# ethernet_ipphone_sch.net
KiCad netlist of a schematic drawn in Altium Designer
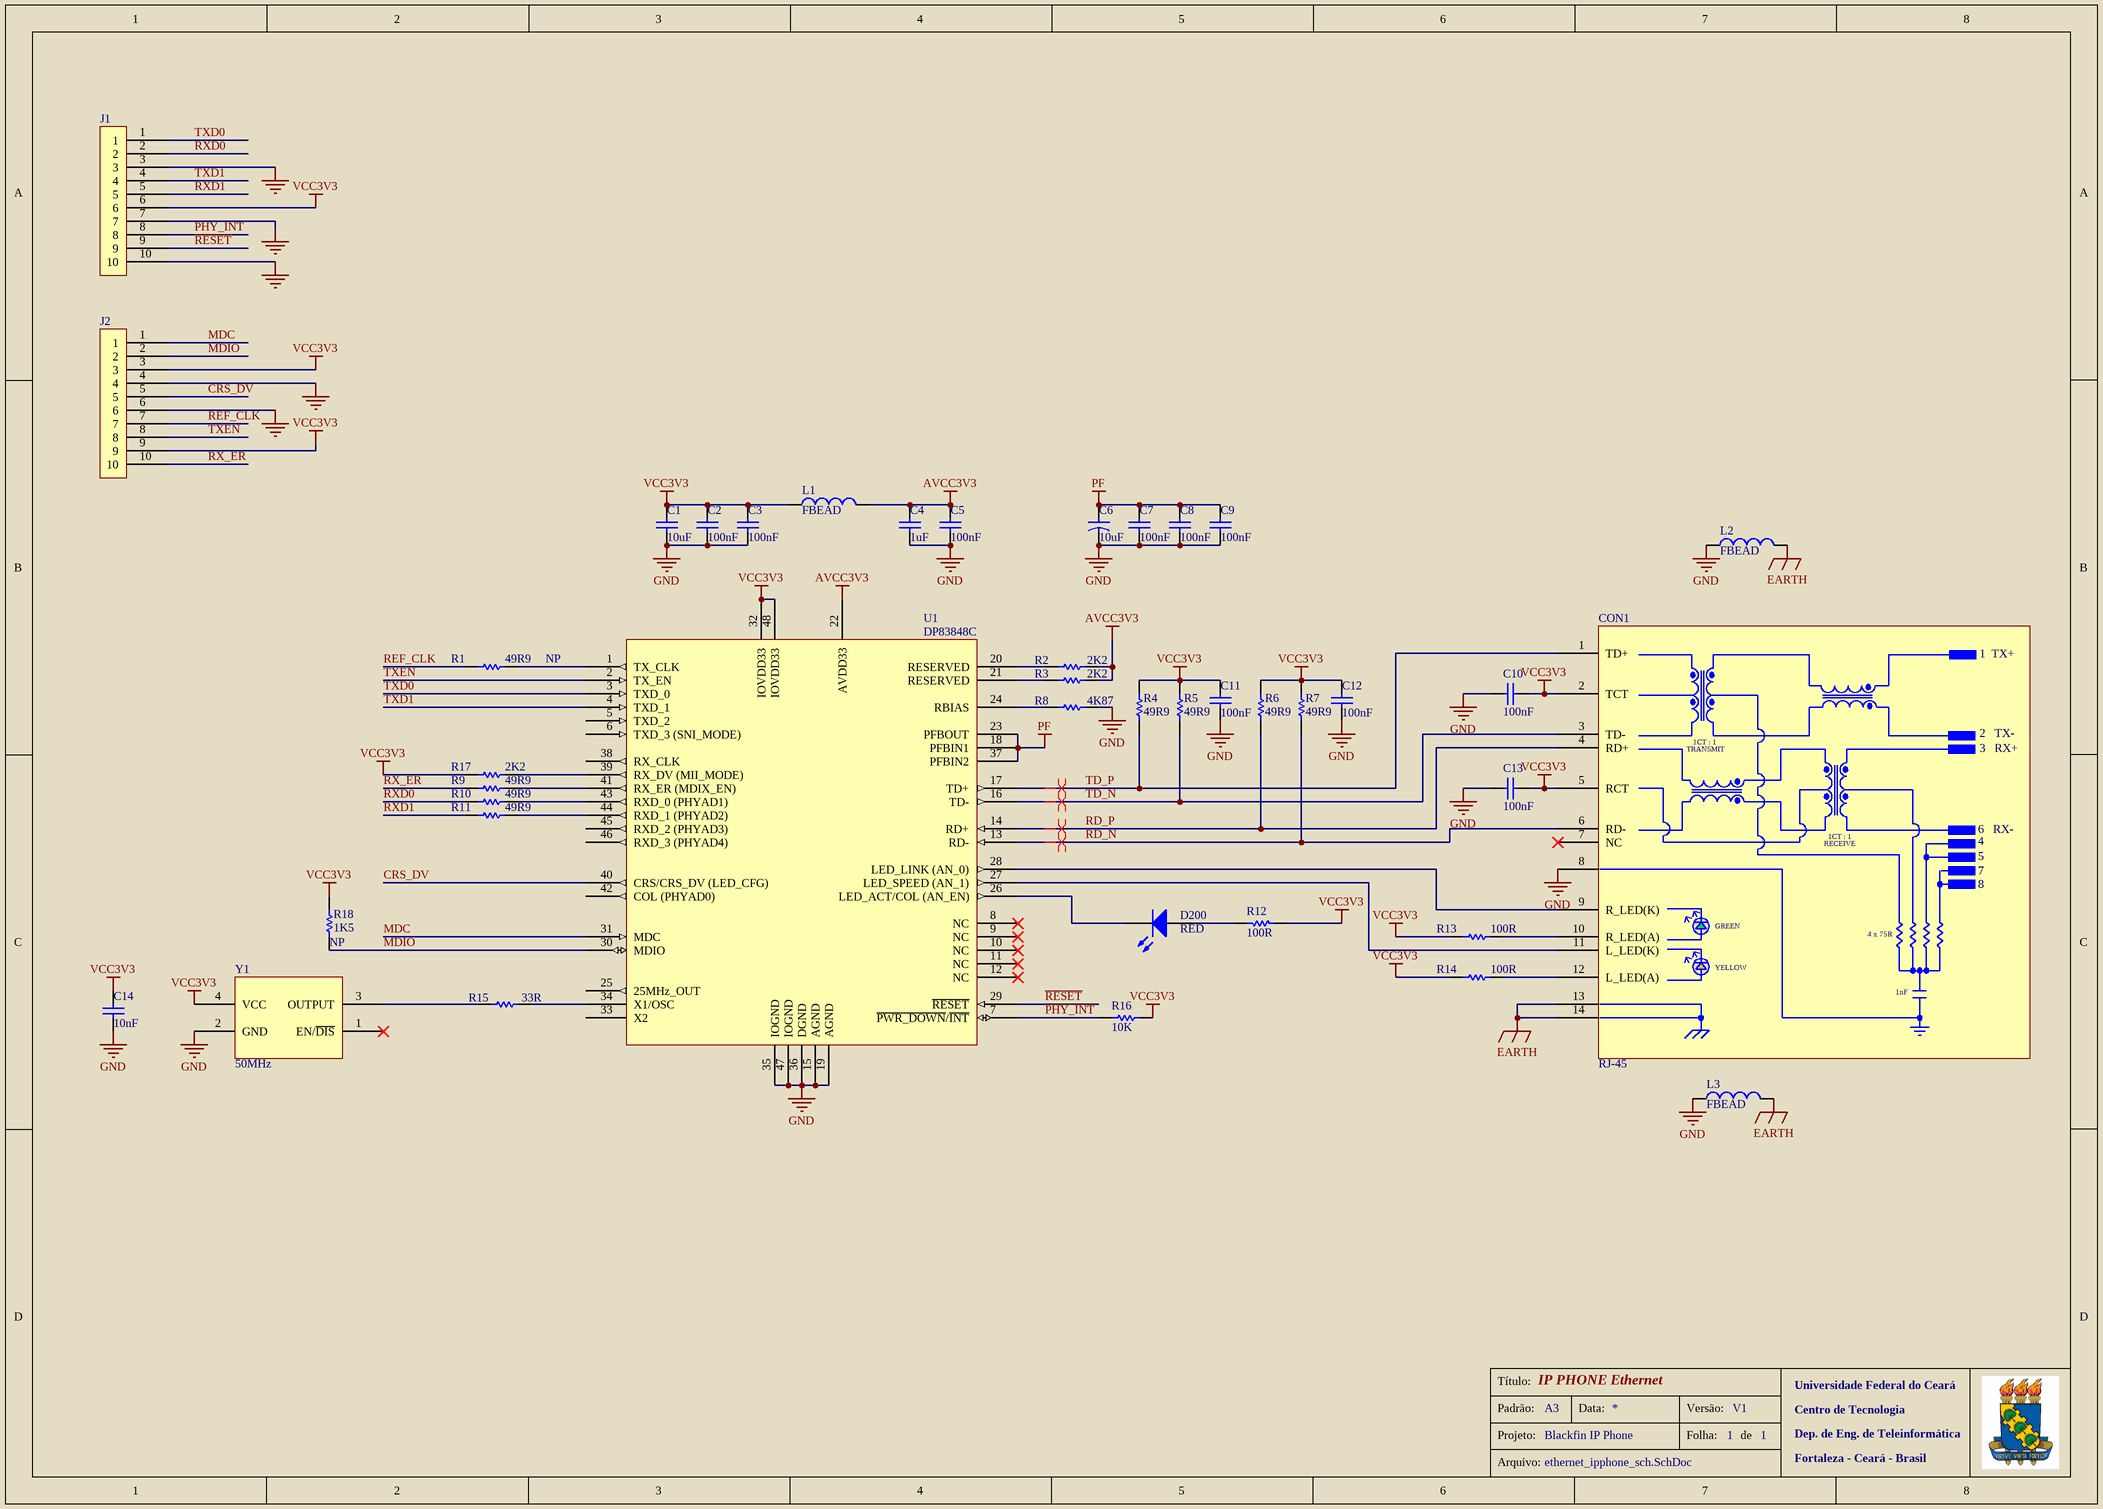
[diagram p0: ethernet_ipphone_sch.SchDoc]

(export (version "E")
  (design (tool "Eeschema 10.0.6"))
  (components
    (comp (ref "C1")
      (value "10uF")
      (footprint "ip_phone:CC2012-0805")
      (description "Capacitor SMD/SMT 0603 10uF 6.3volts X5R 20%")
      (fields (field (name "EVENDORPART#") "810-C2012Y5V1A106Z") (field (name "MANUFACTURER") "TDK"))
      (libsource (lib "ip_phone") (part "Capacitor"))
    )
    (comp (ref "C2")
      (value "100nF")
      (footprint "ip_phone:CC1005-0402")
      (description "MLCC - SMD/SMT 0.1UF 16V 10% 0402")
      (fields (field (name "EVENDORPART#") "810-C1005X7R1C104K") (field (name "MANUFACTURER") "TDK"))
      (libsource (lib "ip_phone") (part "Capacitor"))
    )
    (comp (ref "C3")
      (value "100nF")
      (footprint "ip_phone:CC1005-0402")
      (description "MLCC - SMD/SMT 0.1UF 16V 10% 0402")
      (fields (field (name "EVENDORPART#") "810-C1005X7R1C104K") (field (name "MANUFACTURER") "TDK"))
      (libsource (lib "ip_phone") (part "Capacitor"))
    )
    (comp (ref "C4")
      (value "1uF")
      (footprint "ip_phone:CC1608-0603")
      (description "SMD/SMT 0603 1uF 25volts Y5V +80-20%")
      (fields (field (name "EVENDORPART#") "81-GRM188F51E105ZA12") (field (name "MANUFACTURER") "Murata"))
      (libsource (lib "ip_phone") (part "Capacitor"))
    )
    (comp (ref "C5")
      (value "100nF")
      (footprint "ip_phone:CC1005-0402")
      (description "MLCC - SMD/SMT 0.1UF 16V 10% 0402")
      (fields (field (name "EVENDORPART#") "810-C1005X7R1C104K") (field (name "MANUFACTURER") "TDK"))
      (libsource (lib "ip_phone") (part "Capacitor"))
    )
    (comp (ref "C6")
      (value "10uF")
      (footprint "ip_phone:C_Case_A")
      (description "Tantalum Capacitors - Solid SMD 16volts 10uF 10%")
      (fields (field (name "EVENDORPART#") "80-B45196H3106K109") (field (name "PART#") "B45196H3106K109V17"))
      (libsource (lib "ip_phone") (part "Capacitor_Tan"))
    )
    (comp (ref "C7")
      (value "100nF")
      (footprint "ip_phone:CC1005-0402")
      (description "MLCC - SMD/SMT 0.1UF 16V 10% 0402")
      (fields (field (name "EVENDORPART#") "810-C1005X7R1C104K") (field (name "MANUFACTURER") "TDK"))
      (libsource (lib "ip_phone") (part "Capacitor"))
    )
    (comp (ref "C8")
      (value "100nF")
      (footprint "ip_phone:CC1005-0402")
      (description "MLCC - SMD/SMT 0.1UF 16V 10% 0402")
      (fields (field (name "EVENDORPART#") "810-C1005X7R1C104K") (field (name "MANUFACTURER") "TDK"))
      (libsource (lib "ip_phone") (part "Capacitor"))
    )
    (comp (ref "C9")
      (value "100nF")
      (footprint "ip_phone:CC1005-0402")
      (description "MLCC - SMD/SMT 0.1UF 16V 10% 0402")
      (fields (field (name "EVENDORPART#") "810-C1005X7R1C104K") (field (name "MANUFACTURER") "TDK"))
      (libsource (lib "ip_phone") (part "Capacitor"))
    )
    (comp (ref "C10")
      (value "100nF")
      (footprint "ip_phone:CC1005-0402")
      (description "MLCC - SMD/SMT 0.1UF 16V 10% 0402")
      (fields (field (name "EVENDORPART#") "810-C1005X7R1C104K") (field (name "MANUFACTURER") "TDK"))
      (libsource (lib "ip_phone") (part "Capacitor"))
    )
    (comp (ref "C11")
      (value "100nF")
      (footprint "ip_phone:CC1005-0402")
      (description "MLCC - SMD/SMT 0.1UF 16V 10% 0402")
      (fields (field (name "EVENDORPART#") "810-C1005X7R1C104K") (field (name "MANUFACTURER") "TDK"))
      (libsource (lib "ip_phone") (part "Capacitor"))
    )
    (comp (ref "C12")
      (value "100nF")
      (footprint "ip_phone:CC1005-0402")
      (description "MLCC - SMD/SMT 0.1UF 16V 10% 0402")
      (fields (field (name "EVENDORPART#") "810-C1005X7R1C104K") (field (name "MANUFACTURER") "TDK"))
      (libsource (lib "ip_phone") (part "Capacitor"))
    )
    (comp (ref "C13")
      (value "100nF")
      (footprint "ip_phone:CC1005-0402")
      (description "MLCC - SMD/SMT 0.1UF 16V 10% 0402")
      (fields (field (name "EVENDORPART#") "810-C1005X7R1C104K") (field (name "MANUFACTURER") "TDK"))
      (libsource (lib "ip_phone") (part "Capacitor"))
    )
    (comp (ref "C14")
      (value "10nF")
      (footprint "ip_phone:CC1005-0402")
      (description "Capacitor SMD/SMT 0402 0.01uF 16volts X7R 10%")
      (fields (field (name "EVENDORPART#") "810-C1005X7R1C103K") (field (name "MANUFACTURER") "TDK"))
      (libsource (lib "ip_phone") (part "Capacitor"))
    )
    (comp (ref "CON1")
      (value "RJ-45")
      (footprint "ip_phone:RJ-45")
      (description "Ethernet & Telecom Connectors 1X1 RJ45 JACK")
      (fields (field (name "EVENDORPART#") "673-J1012F01C") (field (name "PART#") "J1012F01C"))
      (libsource (lib "ip_phone") (part "RJ-45"))
    )
    (comp (ref "D200")
      (value "RED")
      (footprint "ip_phone:LED_0603")
      (description "LED")
      (fields (field (name "PART#") "APT1608SURCK") (field (name "MANUFACTURER") "Kingbright"))
      (libsource (lib "ip_phone") (part "LED"))
    )
    (comp (ref "J1")
      (value "CONN HEADER")
      (footprint "ip_phone:CONECTOR_10_PIN")
      (description "CONN HEADER .050\" 10POS PCB GOLD")
      (fields
        (field (name "EVENDORPART#") "S9014E-10-ND")
        (field (name "MANUFACTURER") "Sullins Connector Solutions")
      )
      (libsource (lib "ip_phone") (part "Conector 10pin"))
    )
    (comp (ref "J2")
      (value "CONN HEADER")
      (footprint "ip_phone:CONECTOR_10_PIN")
      (description "CONN HEADER .050\" 10POS PCB GOLD")
      (fields
        (field (name "EVENDORPART#") "S9014E-10-ND")
        (field (name "MANUFACTURER") "Sullins Connector Solutions")
      )
      (libsource (lib "ip_phone") (part "Conector 10pin"))
    )
    (comp (ref "L1")
      (value "FBEAD")
      (footprint "ip_phone:INDUTOR_0603")
      (description "EMI Filter Beads, Chokes & Arrays 300ohms 100MHz 2A Monolithic 0603 SMD")
      (fields
        (field (name "EVENDORPART#") "875-MI0603L301R-10")
        (field (name "MANUFACTURER") "Laird Technologies")
      )
      (libsource (lib "ip_phone") (part "Inductor"))
    )
    (comp (ref "L2")
      (value "FBEAD")
      (footprint "ip_phone:INDUTOR_0603")
      (description "EMI Filter Beads, Chokes & Arrays 300ohms 100MHz 2A Monolithic 0603 SMD")
      (fields
        (field (name "EVENDORPART#") "875-MI0603L301R-10")
        (field (name "MANUFACTURER") "Laird Technologies")
      )
      (libsource (lib "ip_phone") (part "Inductor"))
    )
    (comp (ref "L3")
      (value "FBEAD")
      (footprint "ip_phone:INDUTOR_0603")
      (description "EMI Filter Beads, Chokes & Arrays 300ohms 100MHz 2A Monolithic 0603 SMD")
      (fields
        (field (name "EVENDORPART#") "875-MI0603L301R-10")
        (field (name "MANUFACTURER") "Laird Technologies")
      )
      (libsource (lib "ip_phone") (part "Inductor"))
    )
    (comp (ref "R1")
      (value "49R9")
      (footprint "ip_phone:CR1005-0402_NP")
      (description "Thick Film Resistors - SMD 1/16watt 49.9ohms 1% 0402")
      (fields
        (field (name "EVENDORPART#") "71-CRCW0402-49.9-E3")
        (field (name "MANUFACTURER") "Vishay/Dale")
        (field (name "NP") "NP")
      )
      (libsource (lib "ip_phone") (part "Resistor"))
    )
    (comp (ref "R2")
      (value "2K2")
      (footprint "ip_phone:CR1005-0402")
      (description "Thick Film Resistors SMD 0402 2K2 5%  1/16 W")
      (fields (field (name "EVENDORPART#") "311-2.2KJRCT-ND") (field (name "MANUFACTURER") "Yageo"))
      (libsource (lib "ip_phone") (part "Resistor"))
    )
    (comp (ref "R3")
      (value "2K2")
      (footprint "ip_phone:CR1005-0402")
      (description "Thick Film Resistors SMD 0402 2K2 5%  1/16 W")
      (fields (field (name "EVENDORPART#") "311-2.2KJRCT-ND") (field (name "MANUFACTURER") "Yageo"))
      (libsource (lib "ip_phone") (part "Resistor"))
    )
    (comp (ref "R4")
      (value "49R9")
      (footprint "ip_phone:CR1005-0402")
      (description "Thick Film Resistors - SMD 1/16watt 49.9ohms 1% 0402")
      (fields (field (name "EVENDORPART#") "71-CRCW0402-49.9-E3") (field (name "MANUFACTURER") "Vishay/Dale"))
      (libsource (lib "ip_phone") (part "Resistor"))
    )
    (comp (ref "R5")
      (value "49R9")
      (footprint "ip_phone:CR1005-0402")
      (description "Thick Film Resistors - SMD 1/16watt 49.9ohms 1% 0402")
      (fields (field (name "EVENDORPART#") "71-CRCW0402-49.9-E3") (field (name "MANUFACTURER") "Vishay/Dale"))
      (libsource (lib "ip_phone") (part "Resistor"))
    )
    (comp (ref "R6")
      (value "49R9")
      (footprint "ip_phone:CR1005-0402")
      (description "Thick Film Resistors - SMD 1/16watt 49.9ohms 1% 0402")
      (fields (field (name "EVENDORPART#") "71-CRCW0402-49.9-E3") (field (name "MANUFACTURER") "Vishay/Dale"))
      (libsource (lib "ip_phone") (part "Resistor"))
    )
    (comp (ref "R7")
      (value "49R9")
      (footprint "ip_phone:CR1005-0402")
      (description "Thick Film Resistors - SMD 1/16watt 49.9ohms 1% 0402")
      (fields (field (name "EVENDORPART#") "71-CRCW0402-49.9-E3") (field (name "MANUFACTURER") "Vishay/Dale"))
      (libsource (lib "ip_phone") (part "Resistor"))
    )
    (comp (ref "R8")
      (value "4K87")
      (footprint "ip_phone:CR1608-0603")
      (description "SMD 1/10watt 4.87Kohms 1% 0603")
      (fields
        (field (name "EVENDORPART#") "71-CRCW0603-4.87K-E3")
        (field (name "MANUFACTURER") "Vishay/Dale")
      )
      (libsource (lib "ip_phone") (part "Resistor"))
    )
    (comp (ref "R9")
      (value "49R9")
      (footprint "ip_phone:CR1005-0402")
      (description "Thick Film Resistors - SMD 1/16watt 49.9ohms 1% 0402")
      (fields (field (name "EVENDORPART#") "71-CRCW0402-49.9-E3") (field (name "MANUFACTURER") "Vishay/Dale"))
      (libsource (lib "ip_phone") (part "Resistor"))
    )
    (comp (ref "R10")
      (value "49R9")
      (footprint "ip_phone:CR1005-0402")
      (description "Thick Film Resistors - SMD 1/16watt 49.9ohms 1% 0402")
      (fields (field (name "EVENDORPART#") "71-CRCW0402-49.9-E3") (field (name "MANUFACTURER") "Vishay/Dale"))
      (libsource (lib "ip_phone") (part "Resistor"))
    )
    (comp (ref "R11")
      (value "49R9")
      (footprint "ip_phone:CR1005-0402")
      (description "Thick Film Resistors - SMD 1/16watt 49.9ohms 1% 0402")
      (fields (field (name "EVENDORPART#") "71-CRCW0402-49.9-E3") (field (name "MANUFACTURER") "Vishay/Dale"))
      (libsource (lib "ip_phone") (part "Resistor"))
    )
    (comp (ref "R12")
      (value "100R")
      (footprint "ip_phone:CR1608-0603")
      (description "Thick Film Resistors 1/16WATT 100R 0402")
      (fields (field (name "EVENDORPART#") "652-CR0603-JW-101GLF") (field (name "MANUFACTURER") "Bourns"))
      (libsource (lib "ip_phone") (part "Resistor"))
    )
    (comp (ref "R13")
      (value "100R")
      (footprint "ip_phone:CR1608-0603")
      (description "Thick Film Resistors 1/16WATT 100R 0402")
      (fields (field (name "EVENDORPART#") "652-CR0603-JW-101GLF") (field (name "MANUFACTURER") "Bourns"))
      (libsource (lib "ip_phone") (part "Resistor"))
    )
    (comp (ref "R14")
      (value "100R")
      (footprint "ip_phone:CR1608-0603")
      (description "Thick Film Resistors 1/16WATT 100R 0402")
      (fields (field (name "EVENDORPART#") "652-CR0603-JW-101GLF") (field (name "MANUFACTURER") "Bourns"))
      (libsource (lib "ip_phone") (part "Resistor"))
    )
    (comp (ref "R15")
      (value "33R")
      (footprint "ip_phone:CR1005-0402")
      (description "Thick Film Resistors SMD 0402 33R 5%  1/16 W")
      (fields (field (name "EVENDORPART#") "311-33JRCT-ND") (field (name "MANUFACTURER") "Yageo"))
      (libsource (lib "ip_phone") (part "Resistor"))
    )
    (comp (ref "R16")
      (value "10K")
      (footprint "ip_phone:CR1005-0402")
      (description "Thick Film Resistors SMD 0402 10K 5%  1/16 W")
      (fields (field (name "EVENDORPART#") "311-10KJRCT-ND") (field (name "MANUFACTURER") "Yageo"))
      (libsource (lib "ip_phone") (part "Resistor"))
    )
    (comp (ref "R17")
      (value "2K2")
      (footprint "ip_phone:CR1005-0402")
      (description "Thick Film Resistors SMD 0402 2K2 5%  1/16 W")
      (fields (field (name "EVENDORPART#") "311-2.2KJRCT-ND") (field (name "MANUFACTURER") "Yageo"))
      (libsource (lib "ip_phone") (part "Resistor"))
    )
    (comp (ref "R18")
      (value "1K5")
      (footprint "ip_phone:CR1608-0603")
      (description "Thick Film Resistors 1.5KOHM 5% 1/10W")
      (fields
        (field (name "EVENDORPART#") "52-CR0603-JW-152GLF")
        (field (name "MANUFACTURER") "Bourns")
        (field (name "NP") "NP")
      )
      (libsource (lib "ip_phone") (part "Resistor"))
    )
    (comp (ref "U1")
      (value "DP83848C")
      (footprint "ip_phone:LQFP48")
      (description "IC TXRX ETHERNET PHYTER 48-LQFP")
      (fields (field (name "MANUFACTURER") "National Semiconductor") (field (name "PART#") "DP83848CVV/NOPB"))
      (libsource (lib "ip_phone") (part "DP83848C"))
    )
    (comp (ref "Y1")
      (value "50MHz")
      (footprint "ip_phone:OSC_25MHz_PHY")
      (description "OSC 50.0000 MHZ 3.3V SMD")
      (fields (field (name "EVENDORPART#") "CTX327LVCT-ND") (field (name "PART#") "CB3LV-3I-50M0000"))
      (libsource (lib "ip_phone") (part "Oscillator_25MHz_Phy"))
    )
  )
  (nets
    (net (code "1") (name "/CRS_DV") (class "Default")
      (node (ref "J2") (pin "5") (pinfunction "5_5") (pintype "passive"))
      (node (ref "U1") (pin "40") (pinfunction "CRS/CRS_DV_(LED_CFG)_40") (pintype "output"))
    )
    (net (code "2") (name "/MDC") (class "Default")
      (node (ref "J2") (pin "1") (pinfunction "1_1") (pintype "passive"))
      (node (ref "U1") (pin "31") (pinfunction "MDC_31") (pintype "input"))
    )
    (net (code "3") (name "/MDIO") (class "Default")
      (node (ref "J2") (pin "2") (pinfunction "2_2") (pintype "passive"))
      (node (ref "R18") (pin "2") (pinfunction "2_2") (pintype "passive"))
      (node (ref "U1") (pin "30") (pinfunction "MDIO_30") (pintype "bidirectional"))
    )
    (net (code "4") (name "/RD_N") (class "Default")
      (node (ref "CON1") (pin "6") (pinfunction "RD-_6") (pintype "passive"))
      (node (ref "R7") (pin "1") (pinfunction "1_1") (pintype "passive"))
      (node (ref "U1") (pin "13") (pinfunction "RD-_13") (pintype "input"))
    )
    (net (code "5") (name "/RD_P") (class "Default")
      (node (ref "CON1") (pin "4") (pinfunction "RD+_4") (pintype "passive"))
      (node (ref "R6") (pin "1") (pinfunction "1_1") (pintype "passive"))
      (node (ref "U1") (pin "14") (pinfunction "RD+_14") (pintype "input"))
    )
    (net (code "6") (name "/REF_CLK") (class "Default")
      (node (ref "J2") (pin "7") (pinfunction "7_7") (pintype "passive"))
      (node (ref "R1") (pin "1") (pinfunction "1_1") (pintype "passive"))
    )
    (net (code "7") (name "/RXD0") (class "Default")
      (node (ref "J1") (pin "2") (pinfunction "2_2") (pintype "passive"))
      (node (ref "R10") (pin "1") (pinfunction "1_1") (pintype "passive"))
    )
    (net (code "8") (name "/RXD1") (class "Default")
      (node (ref "J1") (pin "5") (pinfunction "5_5") (pintype "passive"))
      (node (ref "R11") (pin "1") (pinfunction "1_1") (pintype "passive"))
    )
    (net (code "9") (name "/RX_ER") (class "Default")
      (node (ref "J2") (pin "10") (pinfunction "10_10") (pintype "passive"))
      (node (ref "R9") (pin "1") (pinfunction "1_1") (pintype "passive"))
    )
    (net (code "10") (name "/TD_N") (class "Default")
      (node (ref "CON1") (pin "3") (pinfunction "TD-_3") (pintype "passive"))
      (node (ref "R5") (pin "1") (pinfunction "1_1") (pintype "passive"))
      (node (ref "U1") (pin "16") (pinfunction "TD-_16") (pintype "output"))
    )
    (net (code "11") (name "/TD_P") (class "Default")
      (node (ref "CON1") (pin "1") (pinfunction "TD+_1") (pintype "passive"))
      (node (ref "R4") (pin "1") (pinfunction "1_1") (pintype "passive"))
      (node (ref "U1") (pin "17") (pinfunction "TD+_17") (pintype "output"))
    )
    (net (code "12") (name "/TXD0") (class "Default")
      (node (ref "J1") (pin "1") (pinfunction "1_1") (pintype "passive"))
      (node (ref "U1") (pin "3") (pinfunction "TXD_0_3") (pintype "input"))
    )
    (net (code "13") (name "/TXD1") (class "Default")
      (node (ref "J1") (pin "4") (pinfunction "4_4") (pintype "passive"))
      (node (ref "U1") (pin "4") (pinfunction "TXD_1_4") (pintype "input"))
    )
    (net (code "14") (name "/TXEN") (class "Default")
      (node (ref "J2") (pin "8") (pinfunction "8_8") (pintype "passive"))
      (node (ref "U1") (pin "2") (pinfunction "TX_EN_2") (pintype "input"))
    )
    (net (code "15") (name "/~{PHY_INT}") (class "Default")
      (node (ref "J1") (pin "8") (pinfunction "8_8") (pintype "passive"))
      (node (ref "R16") (pin "2") (pinfunction "2_2") (pintype "passive"))
      (node (ref "U1") (pin "7") (pinfunction "~{PWR_DOWN}/~{INT}_7") (pintype "bidirectional"))
    )
    (net (code "16") (name "/~{RESET}") (class "Default")
      (node (ref "J1") (pin "9") (pinfunction "9_9") (pintype "passive"))
      (node (ref "U1") (pin "29") (pinfunction "~{RESET}_29") (pintype "input"))
    )
    (net (code "17") (name "AVCC3V3") (class "Default")
      (node (ref "C4") (pin "2") (pinfunction "2_2") (pintype "passive"))
      (node (ref "C5") (pin "2") (pinfunction "2_2") (pintype "passive"))
      (node (ref "L1") (pin "2") (pinfunction "2_2") (pintype "passive"))
      (node (ref "R2") (pin "2") (pinfunction "2_2") (pintype "passive"))
      (node (ref "R3") (pin "2") (pinfunction "2_2") (pintype "passive"))
      (node (ref "U1") (pin "22") (pinfunction "AVDD33_22") (pintype "power_in"))
    )
    (net (code "18") (name "EARTH") (class "Default")
      (node (ref "CON1") (pin "13") (pinfunction "GND_13") (pintype "passive"))
      (node (ref "CON1") (pin "14") (pinfunction "GND_14") (pintype "passive"))
      (node (ref "L2") (pin "2") (pinfunction "2_2") (pintype "passive"))
      (node (ref "L3") (pin "2") (pinfunction "2_2") (pintype "passive"))
    )
    (net (code "19") (name "GND") (class "Default")
      (node (ref "C1") (pin "1") (pinfunction "1_1") (pintype "passive"))
      (node (ref "C10") (pin "2") (pinfunction "2_2") (pintype "passive"))
      (node (ref "C11") (pin "1") (pinfunction "1_1") (pintype "passive"))
      (node (ref "C12") (pin "1") (pinfunction "1_1") (pintype "passive"))
      (node (ref "C13") (pin "2") (pinfunction "2_2") (pintype "passive"))
      (node (ref "C14") (pin "1") (pinfunction "1_1") (pintype "passive"))
      (node (ref "C2") (pin "1") (pinfunction "1_1") (pintype "passive"))
      (node (ref "C3") (pin "1") (pinfunction "1_1") (pintype "passive"))
      (node (ref "C4") (pin "1") (pinfunction "1_1") (pintype "passive"))
      (node (ref "C5") (pin "1") (pinfunction "1_1") (pintype "passive"))
      (node (ref "C6") (pin "2") (pinfunction "2_2") (pintype "passive"))
      (node (ref "C7") (pin "1") (pinfunction "1_1") (pintype "passive"))
      (node (ref "C8") (pin "1") (pinfunction "1_1") (pintype "passive"))
      (node (ref "C9") (pin "1") (pinfunction "1_1") (pintype "passive"))
      (node (ref "CON1") (pin "8") (pinfunction "GND_8") (pintype "passive"))
      (node (ref "J1") (pin "10") (pinfunction "10_10") (pintype "passive"))
      (node (ref "J1") (pin "3") (pinfunction "3_3") (pintype "passive"))
      (node (ref "J1") (pin "7") (pinfunction "7_7") (pintype "passive"))
      (node (ref "J2") (pin "4") (pinfunction "4_4") (pintype "passive"))
      (node (ref "J2") (pin "6") (pinfunction "6_6") (pintype "passive"))
      (node (ref "L2") (pin "1") (pinfunction "1_1") (pintype "passive"))
      (node (ref "L3") (pin "1") (pinfunction "1_1") (pintype "passive"))
      (node (ref "R8") (pin "2") (pinfunction "2_2") (pintype "passive"))
      (node (ref "U1") (pin "15") (pinfunction "AGND_15") (pintype "power_in"))
      (node (ref "U1") (pin "19") (pinfunction "AGND_19") (pintype "power_in"))
      (node (ref "U1") (pin "35") (pinfunction "IOGND_35") (pintype "power_in"))
      (node (ref "U1") (pin "36") (pinfunction "DGND_36") (pintype "power_in"))
      (node (ref "U1") (pin "47") (pinfunction "IOGND_47") (pintype "power_in"))
      (node (ref "Y1") (pin "2") (pinfunction "GND_2") (pintype "passive"))
    )
    (net (code "20") (name "Net-(CON1-L_LED(A))") (class "Default")
      (node (ref "CON1") (pin "12") (pinfunction "L_LED(A)_12") (pintype "passive"))
      (node (ref "R14") (pin "1") (pinfunction "1_1") (pintype "passive"))
    )
    (net (code "21") (name "Net-(CON1-L_LED(K))") (class "Default")
      (node (ref "CON1") (pin "11") (pinfunction "L_LED(K)_11") (pintype "passive"))
      (node (ref "U1") (pin "27") (pinfunction "LED_SPEED_(AN_1)_27") (pintype "output"))
    )
    (net (code "22") (name "Net-(CON1-R_LED(A))") (class "Default")
      (node (ref "CON1") (pin "10") (pinfunction "R_LED(A)_10") (pintype "passive"))
      (node (ref "R13") (pin "1") (pinfunction "1_1") (pintype "passive"))
    )
    (net (code "23") (name "Net-(CON1-R_LED(K))") (class "Default")
      (node (ref "CON1") (pin "9") (pinfunction "R_LED(K)_9") (pintype "passive"))
      (node (ref "U1") (pin "28") (pinfunction "LED_LINK_(AN_0)_28") (pintype "output"))
    )
    (net (code "24") (name "Net-(D200-A)") (class "Default")
      (node (ref "D200") (pin "1") (pinfunction "A_1") (pintype "passive"))
      (node (ref "R12") (pin "1") (pinfunction "1_1") (pintype "passive"))
    )
    (net (code "25") (name "Net-(D200-K)") (class "Default")
      (node (ref "D200") (pin "2") (pinfunction "K_2") (pintype "passive"))
      (node (ref "U1") (pin "26") (pinfunction "LED_ACT/COL_(AN_EN)_26") (pintype "output"))
    )
    (net (code "26") (name "Net-(R2-Pad1)") (class "Default")
      (node (ref "R2") (pin "1") (pinfunction "1_1") (pintype "passive"))
      (node (ref "U1") (pin "20") (pinfunction "RESERVED_20") (pintype "passive"))
    )
    (net (code "27") (name "Net-(R3-Pad1)") (class "Default")
      (node (ref "R3") (pin "1") (pinfunction "1_1") (pintype "passive"))
      (node (ref "U1") (pin "21") (pinfunction "RESERVED_21") (pintype "passive"))
    )
    (net (code "28") (name "Net-(U1-RBIAS)") (class "Default")
      (node (ref "R8") (pin "1") (pinfunction "1_1") (pintype "passive"))
      (node (ref "U1") (pin "24") (pinfunction "RBIAS_24") (pintype "passive"))
    )
    (net (code "29") (name "Net-(U1-RXD_0_(PHYAD1))") (class "Default")
      (node (ref "R10") (pin "2") (pinfunction "2_2") (pintype "passive"))
      (node (ref "U1") (pin "43") (pinfunction "RXD_0_(PHYAD1)_43") (pintype "output"))
    )
    (net (code "30") (name "Net-(U1-RXD_1_(PHYAD2))") (class "Default")
      (node (ref "R11") (pin "2") (pinfunction "2_2") (pintype "passive"))
      (node (ref "U1") (pin "44") (pinfunction "RXD_1_(PHYAD2)_44") (pintype "output"))
    )
    (net (code "31") (name "Net-(U1-RX_DV_(MII_MODE))") (class "Default")
      (node (ref "R17") (pin "1") (pinfunction "1_1") (pintype "passive"))
      (node (ref "U1") (pin "39") (pinfunction "RX_DV_(MII_MODE)_39") (pintype "output"))
    )
    (net (code "32") (name "Net-(U1-RX_ER_(MDIX_EN))") (class "Default")
      (node (ref "R9") (pin "2") (pinfunction "2_2") (pintype "passive"))
      (node (ref "U1") (pin "41") (pinfunction "RX_ER_(MDIX_EN)_41") (pintype "output"))
    )
    (net (code "33") (name "Net-(U1-TX_CLK)") (class "Default")
      (node (ref "R1") (pin "2") (pinfunction "2_2") (pintype "passive"))
      (node (ref "U1") (pin "1") (pinfunction "TX_CLK_1") (pintype "output"))
    )
    (net (code "34") (name "Net-(U1-X1{slash}OSC)") (class "Default")
      (node (ref "R15") (pin "2") (pinfunction "2_2") (pintype "passive"))
      (node (ref "U1") (pin "34") (pinfunction "X1/OSC_34") (pintype "passive"))
    )
    (net (code "35") (name "Net-(Y1-OUTPUT)") (class "Default")
      (node (ref "R15") (pin "1") (pinfunction "1_1") (pintype "passive"))
      (node (ref "Y1") (pin "3") (pinfunction "OUTPUT_3") (pintype "passive"))
    )
    (net (code "36") (name "PF") (class "Default")
      (node (ref "C6") (pin "1") (pinfunction "1_1") (pintype "passive"))
      (node (ref "C7") (pin "2") (pinfunction "2_2") (pintype "passive"))
      (node (ref "C8") (pin "2") (pinfunction "2_2") (pintype "passive"))
      (node (ref "C9") (pin "2") (pinfunction "2_2") (pintype "passive"))
      (node (ref "U1") (pin "18") (pinfunction "PFBIN1_18") (pintype "passive"))
      (node (ref "U1") (pin "23") (pinfunction "PFBOUT_23") (pintype "passive"))
      (node (ref "U1") (pin "37") (pinfunction "PFBIN2_37") (pintype "passive"))
    )
    (net (code "37") (name "VCC3V3") (class "Default")
      (node (ref "C1") (pin "2") (pinfunction "2_2") (pintype "passive"))
      (node (ref "C10") (pin "1") (pinfunction "1_1") (pintype "passive"))
      (node (ref "C11") (pin "2") (pinfunction "2_2") (pintype "passive"))
      (node (ref "C12") (pin "2") (pinfunction "2_2") (pintype "passive"))
      (node (ref "C13") (pin "1") (pinfunction "1_1") (pintype "passive"))
      (node (ref "C14") (pin "2") (pinfunction "2_2") (pintype "passive"))
      (node (ref "C2") (pin "2") (pinfunction "2_2") (pintype "passive"))
      (node (ref "C3") (pin "2") (pinfunction "2_2") (pintype "passive"))
      (node (ref "CON1") (pin "2") (pinfunction "TCT_2") (pintype "passive"))
      (node (ref "CON1") (pin "5") (pinfunction "RCT_5") (pintype "passive"))
      (node (ref "J1") (pin "6") (pinfunction "6_6") (pintype "passive"))
      (node (ref "J2") (pin "3") (pinfunction "3_3") (pintype "passive"))
      (node (ref "J2") (pin "9") (pinfunction "9_9") (pintype "passive"))
      (node (ref "L1") (pin "1") (pinfunction "1_1") (pintype "passive"))
      (node (ref "R12") (pin "2") (pinfunction "2_2") (pintype "passive"))
      (node (ref "R13") (pin "2") (pinfunction "2_2") (pintype "passive"))
      (node (ref "R14") (pin "2") (pinfunction "2_2") (pintype "passive"))
      (node (ref "R16") (pin "1") (pinfunction "1_1") (pintype "passive"))
      (node (ref "R17") (pin "2") (pinfunction "2_2") (pintype "passive"))
      (node (ref "R18") (pin "1") (pinfunction "1_1") (pintype "passive"))
      (node (ref "R4") (pin "2") (pinfunction "2_2") (pintype "passive"))
      (node (ref "R5") (pin "2") (pinfunction "2_2") (pintype "passive"))
      (node (ref "R6") (pin "2") (pinfunction "2_2") (pintype "passive"))
      (node (ref "R7") (pin "2") (pinfunction "2_2") (pintype "passive"))
      (node (ref "U1") (pin "32") (pinfunction "IOVDD33_32") (pintype "power_in"))
      (node (ref "U1") (pin "48") (pinfunction "IOVDD33_48") (pintype "power_in"))
      (node (ref "Y1") (pin "4") (pinfunction "VCC_4") (pintype "passive"))
    )
    (net (code "38") (name "unconnected-(CON1-NC-Pad7)") (class "Default")
      (node (ref "CON1") (pin "7") (pinfunction "NC_7") (pintype "passive+no_connect"))
    )
    (net (code "39") (name "unconnected-(U1-25MHz_OUT-Pad25)") (class "Default")
      (node (ref "U1") (pin "25") (pinfunction "25MHz_OUT_25") (pintype "output"))
    )
    (net (code "40") (name "unconnected-(U1-COL_(PHYAD0)-Pad42)") (class "Default")
      (node (ref "U1") (pin "42") (pinfunction "COL_(PHYAD0)_42") (pintype "output"))
    )
    (net (code "41") (name "unconnected-(U1-NC-Pad8)") (class "Default")
      (node (ref "U1") (pin "8") (pinfunction "NC_8") (pintype "passive+no_connect"))
    )
    (net (code "42") (name "unconnected-(U1-NC-Pad9)") (class "Default")
      (node (ref "U1") (pin "9") (pinfunction "NC_9") (pintype "passive+no_connect"))
    )
    (net (code "43") (name "unconnected-(U1-NC-Pad10)") (class "Default")
      (node (ref "U1") (pin "10") (pinfunction "NC_10") (pintype "passive+no_connect"))
    )
    (net (code "44") (name "unconnected-(U1-NC-Pad11)") (class "Default")
      (node (ref "U1") (pin "11") (pinfunction "NC_11") (pintype "passive+no_connect"))
    )
    (net (code "45") (name "unconnected-(U1-NC-Pad12)") (class "Default")
      (node (ref "U1") (pin "12") (pinfunction "NC_12") (pintype "passive+no_connect"))
    )
    (net (code "46") (name "unconnected-(U1-RXD_2_(PHYAD3)-Pad45)") (class "Default")
      (node (ref "U1") (pin "45") (pinfunction "RXD_2_(PHYAD3)_45") (pintype "output"))
    )
    (net (code "47") (name "unconnected-(U1-RXD_3_(PHYAD4)-Pad46)") (class "Default")
      (node (ref "U1") (pin "46") (pinfunction "RXD_3_(PHYAD4)_46") (pintype "output"))
    )
    (net (code "48") (name "unconnected-(U1-RX_CLK-Pad38)") (class "Default")
      (node (ref "U1") (pin "38") (pinfunction "RX_CLK_38") (pintype "output"))
    )
    (net (code "49") (name "unconnected-(U1-TXD_2-Pad5)") (class "Default")
      (node (ref "U1") (pin "5") (pinfunction "TXD_2_5") (pintype "input"))
    )
    (net (code "50") (name "unconnected-(U1-TXD_3_(SNI_MODE)-Pad6)") (class "Default")
      (node (ref "U1") (pin "6") (pinfunction "TXD_3_(SNI_MODE)_6") (pintype "input"))
    )
    (net (code "51") (name "unconnected-(U1-X2-Pad33)") (class "Default")
      (node (ref "U1") (pin "33") (pinfunction "X2_33") (pintype "passive"))
    )
    (net (code "52") (name "unconnected-(Y1-EN{slash}~{DIS}-Pad1)") (class "Default")
      (node (ref "Y1") (pin "1") (pinfunction "EN/~{DIS}_1") (pintype "passive+no_connect"))
    )
  )
)
